# buzzer.net
KiCad netlist of a schematic drawn in Altium Designer
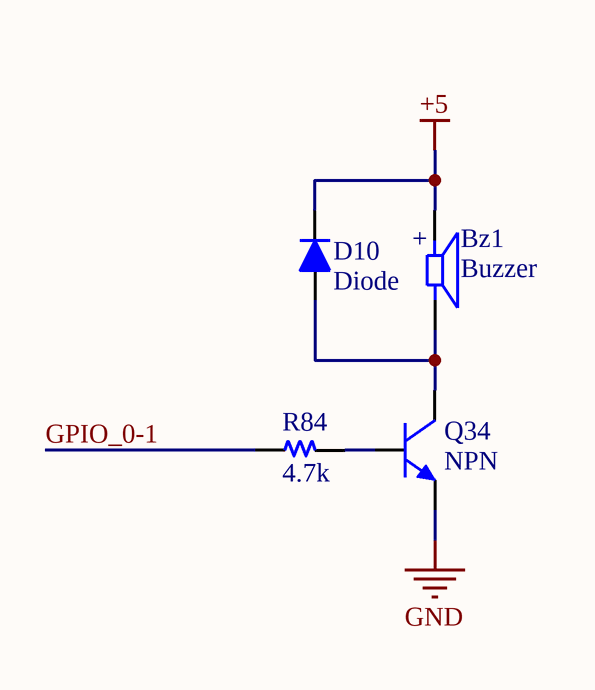
[diagram p0: buzzer.SchDoc]

(export (version "E")
  (design (tool "Eeschema 10.0.6"))
  (components
    (comp (ref "Bz1")
      (value "Buzzer")
      (footprint "CUI_CMT-8530S-SMT")
      (description "8.5 mm, 3.6 Vo-p, 90 dB, Surface Mount _SMT_, Magnetic Audio Transducer Buzzer")
      (fields (field (name "MP") "CMT-8530S-SMT-TR") (field (name "MF") "CUI Devices"))
      (libsource (lib "bs_libs") (part "CMT-8530S-SMT"))
    )
    (comp (ref "D10")
      (value "Diode")
      (footprint "SOD123")
      (description "Default Diode")
      (libsource (lib "chipfc_libs") (part "Diode"))
    )
    (comp (ref "Q34")
      (value "NPN")
      (footprint "SOT-23")
      (description "NPN Bipolar Transistor")
      (libsource (lib "chipfc_libs") (part "Transistor NPN"))
    )
    (comp (ref "R84")
      (value "4.7k")
      (footprint "R 0603")
      (description "Resistor")
      (libsource (lib "chipfc_libs") (part "Resistor"))
    )
  )
  (nets
    (net (code "1") (name "+5") (class "Default")
      (node (ref "Bz1") (pin "P") (pinfunction "P_P") (pintype "passive"))
      (node (ref "D10") (pin "2") (pinfunction "K_2") (pintype "passive"))
    )
    (net (code "2") (name "/GPIO_0-1") (class "Default")
      (node (ref "R84") (pin "1") (pinfunction "1_1") (pintype "passive"))
    )
    (net (code "3") (name "GND") (class "Default")
      (node (ref "Q34") (pin "2") (pinfunction "E_2") (pintype "passive"))
    )
    (net (code "4") (name "Net-(D10-A)") (class "Default")
      (node (ref "Bz1") (pin "N") (pinfunction "N_N") (pintype "passive"))
      (node (ref "D10") (pin "1") (pinfunction "A_1") (pintype "passive"))
      (node (ref "Q34") (pin "3") (pinfunction "C_3") (pintype "passive"))
    )
    (net (code "5") (name "Net-(Q34-B)") (class "Default")
      (node (ref "Q34") (pin "1") (pinfunction "B_1") (pintype "passive"))
      (node (ref "R84") (pin "2") (pinfunction "2_2") (pintype "passive"))
    )
  )
)
